# Sch_LCD.net
KiCad netlist of a schematic drawn in Altium Designer
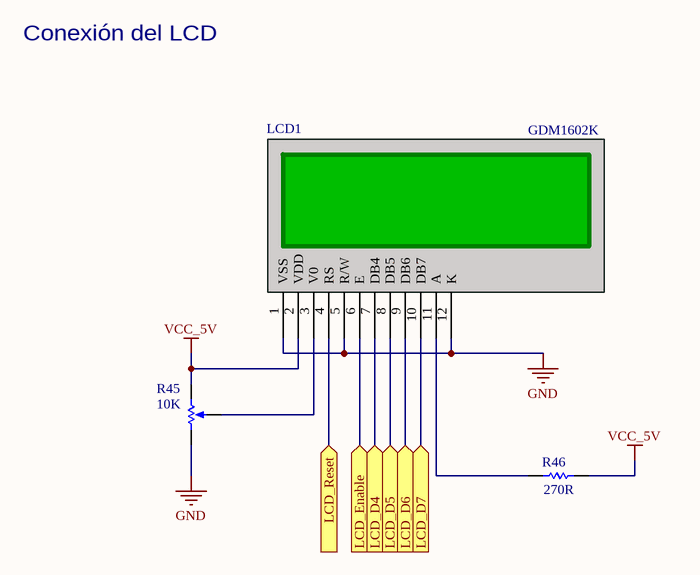
[diagram p0: Sch_LCD.SchDoc]

(export (version "E")
  (design (tool "Eeschema 10.0.6"))
  (components
    (comp (ref "LCD1")
      (value "GDM1602K")
      (footprint "LCD")
      (description "LCD GDM1602K Rev2.2")
      (libsource (lib "Sch_LCD") (part "LCD"))
    )
    (comp (ref "R45")
      (value "10K")
      (footprint "VR5")
      (description "Potentiometer")
      (fields (field (name "Comment") "RPot") (field (name "PUBLISHER") "Altium Limited"))
      (libsource (lib "Miscellaneous Devices") (part "RPot"))
    )
    (comp (ref "R46")
      (value "270R")
      (footprint "AXIAL-0.3")
      (description "Resistor")
      (fields (field (name "Comment") "Res1") (field (name "PUBLISHER") "Altium Limited"))
      (libsource (lib "Miscellaneous Devices") (part "Res1"))
    )
  )
  (nets
    (net (code "1") (name "/LCD_D4") (class "Default")
      (node (ref "LCD1") (pin "7") (pinfunction "DB4_7") (pintype "passive"))
    )
    (net (code "2") (name "/LCD_D5") (class "Default")
      (node (ref "LCD1") (pin "8") (pinfunction "DB5_8") (pintype "passive"))
    )
    (net (code "3") (name "/LCD_D6") (class "Default")
      (node (ref "LCD1") (pin "9") (pinfunction "DB6_9") (pintype "passive"))
    )
    (net (code "4") (name "/LCD_D7") (class "Default")
      (node (ref "LCD1") (pin "10") (pinfunction "DB7_10") (pintype "passive"))
    )
    (net (code "5") (name "/LCD_Enable") (class "Default")
      (node (ref "LCD1") (pin "6") (pinfunction "E_6") (pintype "passive"))
    )
    (net (code "6") (name "/LCD_Reset") (class "Default")
      (node (ref "LCD1") (pin "4") (pinfunction "RS_4") (pintype "passive"))
    )
    (net (code "7") (name "GND") (class "Default")
      (node (ref "LCD1") (pin "1") (pinfunction "VSS_1") (pintype "passive"))
      (node (ref "LCD1") (pin "12") (pinfunction "K_12") (pintype "passive"))
      (node (ref "LCD1") (pin "5") (pinfunction "R/W_5") (pintype "passive"))
      (node (ref "R45") (pin "1") (pinfunction "TOP_1") (pintype "passive"))
    )
    (net (code "8") (name "Net-(LCD1-A)") (class "Default")
      (node (ref "LCD1") (pin "11") (pinfunction "A_11") (pintype "passive"))
      (node (ref "R46") (pin "1") (pinfunction "1_1") (pintype "passive"))
    )
    (net (code "9") (name "Net-(LCD1-V0)") (class "Default")
      (node (ref "LCD1") (pin "3") (pinfunction "V0_3") (pintype "passive"))
      (node (ref "R45") (pin "3") (pinfunction "TAP_3") (pintype "passive"))
    )
    (net (code "10") (name "VCC_5V") (class "Default")
      (node (ref "LCD1") (pin "2") (pinfunction "VDD_2") (pintype "passive"))
      (node (ref "R45") (pin "2") (pinfunction "BOT_2") (pintype "passive"))
      (node (ref "R46") (pin "2") (pinfunction "2_2") (pintype "passive"))
    )
  )
)
